# Sheet1.net
KiCad netlist of a schematic drawn in Altium Designer
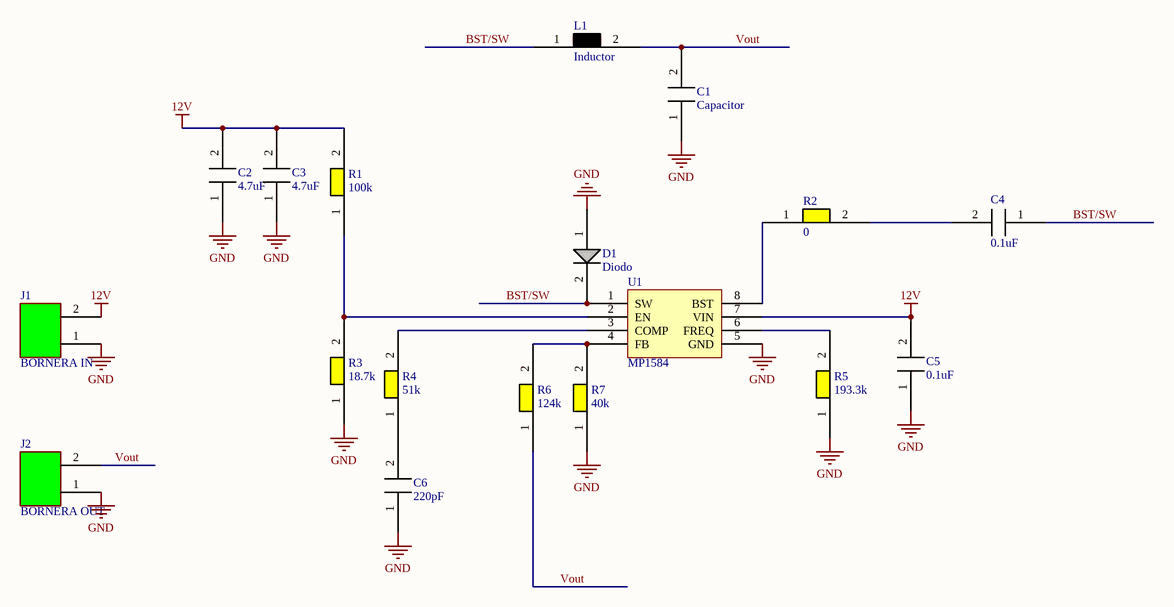
[diagram p0: Sheet1.SchDoc]

(export (version "E")
  (design (tool "Eeschema 10.0.6"))
  (components
    (comp (ref "C1")
      (value "Capacitor")
      (footprint "0805")
      (libsource (lib "LibreriaEsquematico") (part "Capacitor"))
    )
    (comp (ref "C2")
      (value "4.7uF")
      (footprint "0805")
      (libsource (lib "LibreriaEsquematico") (part "Capacitor"))
    )
    (comp (ref "C3")
      (value "4.7uF")
      (footprint "0805")
      (libsource (lib "LibreriaEsquematico") (part "Capacitor"))
    )
    (comp (ref "C4")
      (value "0.1uF")
      (footprint "0805")
      (libsource (lib "LibreriaEsquematico") (part "Capacitor"))
    )
    (comp (ref "C5")
      (value "0.1uF")
      (footprint "0805")
      (libsource (lib "LibreriaEsquematico") (part "Capacitor"))
    )
    (comp (ref "C6")
      (value "220pF")
      (footprint "0805")
      (libsource (lib "LibreriaEsquematico") (part "Capacitor"))
    )
    (comp (ref "D1") (value "Diodo") (footprint "SMA") (libsource (lib "LibreriaEsquematico") (part "Diodo")))
    (comp (ref "J1")
      (value "BORNERA IN")
      (footprint "Bornera")
      (libsource (lib "LibreriaEsquematico") (part "Bornera"))
    )
    (comp (ref "J2")
      (value "BORNERA OUT")
      (footprint "Bornera")
      (libsource (lib "LibreriaEsquematico") (part "Bornera"))
    )
    (comp (ref "L1")
      (value "Inductor")
      (footprint "SMT")
      (libsource (lib "LibreriaEsquematico") (part "Inductor"))
    )
    (comp (ref "R1") (value "100k") (footprint "0805") (libsource (lib "") (part "Resistencia_1")))
    (comp (ref "R2")
      (value "0")
      (footprint "0805")
      (libsource (lib "LibreriaEsquematico") (part "Resistencia"))
    )
    (comp (ref "R3") (value "18.7k") (footprint "0805") (libsource (lib "") (part "Resistencia_1")))
    (comp (ref "R4") (value "51k") (footprint "0805") (libsource (lib "") (part "Resistencia_1")))
    (comp (ref "R5") (value "193.3k") (footprint "0805") (libsource (lib "") (part "Resistencia_1")))
    (comp (ref "R6") (value "124k") (footprint "0805") (libsource (lib "") (part "Resistencia_1")))
    (comp (ref "R7") (value "40k") (footprint "0805") (libsource (lib "") (part "Resistencia_1")))
    (comp (ref "U1")
      (value "MP1584")
      (footprint "SOP8")
      (description "CHIP DE FUENTE")
      (libsource (lib "LibreriaEsquematico") (part "MP1584"))
    )
  )
  (nets
    (net (code "1") (name "/BST{slash}SW") (class "Default")
      (node (ref "C4") (pin "1") (pintype "passive"))
      (node (ref "D1") (pin "2") (pintype "passive"))
      (node (ref "L1") (pin "1") (pintype "passive"))
      (node (ref "U1") (pin "1") (pinfunction "SW_1") (pintype "passive"))
    )
    (net (code "2") (name "/Vout") (class "Default")
      (node (ref "C1") (pin "2") (pintype "passive"))
      (node (ref "J2") (pin "2") (pintype "passive"))
      (node (ref "L1") (pin "2") (pintype "passive"))
      (node (ref "R6") (pin "1") (pintype "passive"))
    )
    (net (code "3") (name "12V") (class "Default")
      (node (ref "C2") (pin "2") (pintype "passive"))
      (node (ref "C3") (pin "2") (pintype "passive"))
      (node (ref "C5") (pin "2") (pintype "passive"))
      (node (ref "J1") (pin "2") (pintype "passive"))
      (node (ref "R1") (pin "2") (pintype "passive"))
      (node (ref "U1") (pin "7") (pinfunction "VIN_7") (pintype "passive"))
    )
    (net (code "4") (name "GND") (class "Default")
      (node (ref "C1") (pin "1") (pintype "passive"))
      (node (ref "C2") (pin "1") (pintype "passive"))
      (node (ref "C3") (pin "1") (pintype "passive"))
      (node (ref "C5") (pin "1") (pintype "passive"))
      (node (ref "C6") (pin "1") (pintype "passive"))
      (node (ref "D1") (pin "1") (pintype "passive"))
      (node (ref "J1") (pin "1") (pintype "passive"))
      (node (ref "J2") (pin "1") (pintype "passive"))
      (node (ref "R3") (pin "1") (pintype "passive"))
      (node (ref "R5") (pin "1") (pintype "passive"))
      (node (ref "R7") (pin "1") (pintype "passive"))
      (node (ref "U1") (pin "5") (pinfunction "GND_5") (pintype "passive"))
    )
    (net (code "5") (name "Net-(C4-Pad2)") (class "Default")
      (node (ref "C4") (pin "2") (pintype "passive"))
      (node (ref "R2") (pin "2") (pintype "passive"))
    )
    (net (code "6") (name "Net-(C6-Pad2)") (class "Default")
      (node (ref "C6") (pin "2") (pintype "passive"))
      (node (ref "R4") (pin "1") (pintype "passive"))
    )
    (net (code "7") (name "Net-(U1-BST)") (class "Default")
      (node (ref "R2") (pin "1") (pintype "passive"))
      (node (ref "U1") (pin "8") (pinfunction "BST_8") (pintype "passive"))
    )
    (net (code "8") (name "Net-(U1-COMP)") (class "Default")
      (node (ref "R4") (pin "2") (pintype "passive"))
      (node (ref "U1") (pin "3") (pinfunction "COMP_3") (pintype "passive"))
    )
    (net (code "9") (name "Net-(U1-EN)") (class "Default")
      (node (ref "R1") (pin "1") (pintype "passive"))
      (node (ref "R3") (pin "2") (pintype "passive"))
      (node (ref "U1") (pin "2") (pinfunction "EN_2") (pintype "passive"))
    )
    (net (code "10") (name "Net-(U1-FB)") (class "Default")
      (node (ref "R6") (pin "2") (pintype "passive"))
      (node (ref "R7") (pin "2") (pintype "passive"))
      (node (ref "U1") (pin "4") (pinfunction "FB_4") (pintype "passive"))
    )
    (net (code "11") (name "Net-(U1-FREQ)") (class "Default")
      (node (ref "R5") (pin "2") (pintype "passive"))
      (node (ref "U1") (pin "6") (pinfunction "FREQ_6") (pintype "passive"))
    )
  )
)
